# Micro_controller_Board_AS-2.net
KiCad netlist of a schematic drawn in EAGLE
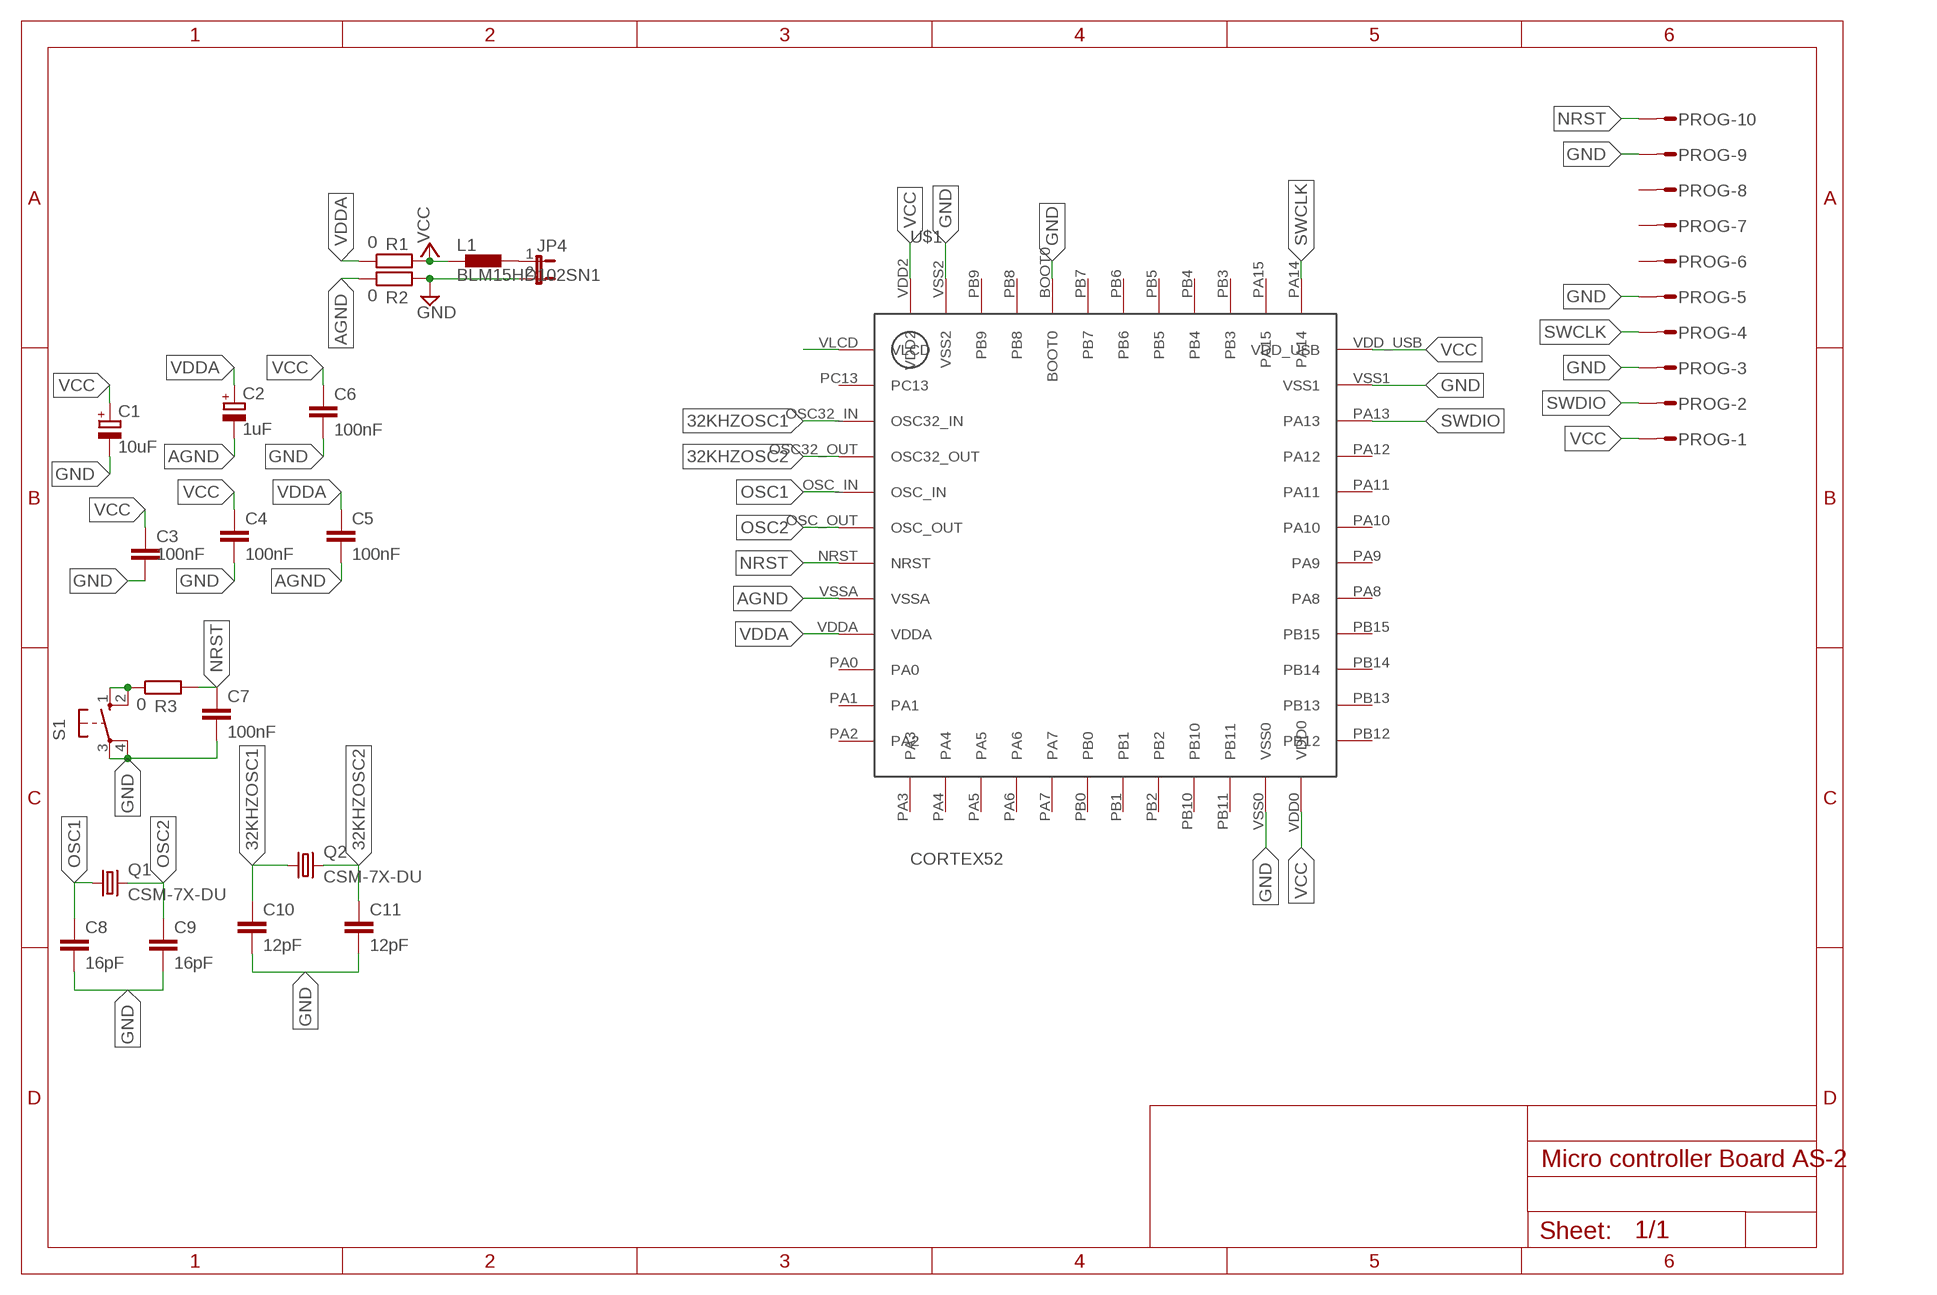
[diagram p0: schematic, sheet 1]

(export (version "E")
  (design (tool "Eeschema 10.0.6"))
  (components
    (comp (ref "C1")
      (value "10uF")
      (footprint "eagle-import:139CLL-2R")
      (libsource (lib "eagle-import") (part "CPOL-EU139CLL-2R"))
    )
    (comp (ref "C2")
      (value "1uF")
      (footprint "eagle-import:139CLL-2R")
      (libsource (lib "eagle-import") (part "CPOL-EU139CLL-2R"))
    )
    (comp (ref "C3")
      (value "100nF")
      (footprint "eagle-import:C0805")
      (libsource (lib "eagle-import") (part "C-EUC0805"))
    )
    (comp (ref "C4")
      (value "100nF")
      (footprint "eagle-import:C0805")
      (libsource (lib "eagle-import") (part "C-EUC0805"))
    )
    (comp (ref "C5")
      (value "100nF")
      (footprint "eagle-import:C0805")
      (libsource (lib "eagle-import") (part "C-EUC0805"))
    )
    (comp (ref "C6")
      (value "100nF")
      (footprint "eagle-import:C0805")
      (libsource (lib "eagle-import") (part "C-EUC0805"))
    )
    (comp (ref "C7")
      (value "100nF")
      (footprint "eagle-import:C0805")
      (libsource (lib "eagle-import") (part "C-EUC0805"))
    )
    (comp (ref "C8")
      (value "16pF")
      (footprint "eagle-import:C0805")
      (libsource (lib "eagle-import") (part "C-EUC0805"))
    )
    (comp (ref "C9")
      (value "16pF")
      (footprint "eagle-import:C0805")
      (libsource (lib "eagle-import") (part "C-EUC0805"))
    )
    (comp (ref "C10")
      (value "12pF")
      (footprint "eagle-import:C0805")
      (libsource (lib "eagle-import") (part "C-EUC0805"))
    )
    (comp (ref "C11")
      (value "12pF")
      (footprint "eagle-import:C0805")
      (libsource (lib "eagle-import") (part "C-EUC0805"))
    )
    (comp (ref "JP4")
      (value "JP1E")
      (footprint "eagle-import:JP1")
      (libsource (lib "eagle-import") (part "JP1E"))
    )
    (comp (ref "L1")
      (value "BLM15HD102SN1")
      (footprint "eagle-import:0402")
      (libsource (lib "eagle-import") (part "BLM15HD102SN1"))
    )
    (comp (ref "PROG")
      (value "S10P")
      (footprint "eagle-import:S10P")
      (libsource (lib "eagle-import") (part "S10P"))
    )
    (comp (ref "Q1")
      (value "CSM-7X-DU")
      (footprint "eagle-import:CSM-7X-DU")
      (libsource (lib "eagle-import") (part "CSM-7X-DU"))
    )
    (comp (ref "Q2")
      (value "CSM-7X-DU")
      (footprint "eagle-import:CSM-7X-DU")
      (libsource (lib "eagle-import") (part "CSM-7X-DU"))
    )
    (comp (ref "R1")
      (value "0")
      (footprint "eagle-import:R0805")
      (libsource (lib "eagle-import") (part "R-EU_R0805"))
    )
    (comp (ref "R2")
      (value "0")
      (footprint "eagle-import:R0805")
      (libsource (lib "eagle-import") (part "R-EU_R0805"))
    )
    (comp (ref "R3")
      (value "0")
      (footprint "eagle-import:R0805")
      (libsource (lib "eagle-import") (part "R-EU_R0805"))
    )
    (comp (ref "S1")
      (value "10-XX")
      (footprint "eagle-import:B3F-10XX")
      (fields (field (name "MPN") "B3F-1000"))
      (libsource (lib "eagle-import") (part "10-XX"))
    )
    (comp (ref "U$1")
      (value "CORTEX52")
      (footprint "eagle-import:CORTEX52")
      (libsource (lib "eagle-import") (part "CORTEX52"))
    )
  )
  (nets
    (net (code "1") (name "32KHZOSC1") (class "Default")
      (node (ref "C10") (pin "1") (pinfunction "1_1") (pintype "passive"))
      (node (ref "Q2") (pin "1") (pinfunction "1_1") (pintype "passive"))
      (node (ref "U$1") (pin "OSC32_IN") (pinfunction "OSC32_IN_OSC32_IN") (pintype "bidirectional"))
    )
    (net (code "2") (name "32KHZOSC2") (class "Default")
      (node (ref "C11") (pin "1") (pinfunction "1_1") (pintype "passive"))
      (node (ref "Q2") (pin "2") (pinfunction "2_2") (pintype "passive"))
      (node (ref "U$1") (pin "OSC32_OUT") (pinfunction "OSC32_OUT_OSC32_OUT") (pintype "bidirectional"))
    )
    (net (code "3") (name "AGND") (class "Default")
      (node (ref "C2") (pin "-") (pinfunction "-_-") (pintype "passive"))
      (node (ref "C5") (pin "2") (pinfunction "2_2") (pintype "passive"))
      (node (ref "R2") (pin "1") (pinfunction "1_1") (pintype "passive"))
      (node (ref "U$1") (pin "VSSA") (pinfunction "VSSA_VSSA") (pintype "bidirectional"))
    )
    (net (code "4") (name "GND") (class "Default")
      (node (ref "C1") (pin "-") (pinfunction "-_-") (pintype "passive"))
      (node (ref "C10") (pin "2") (pinfunction "2_2") (pintype "passive"))
      (node (ref "C11") (pin "2") (pinfunction "2_2") (pintype "passive"))
      (node (ref "C3") (pin "2") (pinfunction "2_2") (pintype "passive"))
      (node (ref "C4") (pin "2") (pinfunction "2_2") (pintype "passive"))
      (node (ref "C6") (pin "2") (pinfunction "2_2") (pintype "passive"))
      (node (ref "C7") (pin "2") (pinfunction "2_2") (pintype "passive"))
      (node (ref "C8") (pin "2") (pinfunction "2_2") (pintype "passive"))
      (node (ref "C9") (pin "2") (pinfunction "2_2") (pintype "passive"))
      (node (ref "JP4") (pin "2") (pinfunction "2_2") (pintype "passive"))
      (node (ref "PROG") (pin "3") (pinfunction "S_3") (pintype "passive"))
      (node (ref "PROG") (pin "5") (pinfunction "S_5") (pintype "passive"))
      (node (ref "PROG") (pin "9") (pinfunction "S_9") (pintype "passive"))
      (node (ref "R2") (pin "2") (pinfunction "2_2") (pintype "passive"))
      (node (ref "S1") (pin "3") (pinfunction "P_3") (pintype "passive"))
      (node (ref "S1") (pin "4") (pinfunction "P1_4") (pintype "passive"))
      (node (ref "U$1") (pin "BOOT0") (pinfunction "BOOT0_BOOT0") (pintype "bidirectional"))
      (node (ref "U$1") (pin "VSS0") (pinfunction "VSS0_VSS0") (pintype "bidirectional"))
      (node (ref "U$1") (pin "VSS1") (pinfunction "VSS1_VSS1") (pintype "bidirectional"))
      (node (ref "U$1") (pin "VSS2") (pinfunction "VSS2_VSS2") (pintype "bidirectional"))
    )
    (net (code "5") (name "NRST") (class "Default")
      (node (ref "C7") (pin "1") (pinfunction "1_1") (pintype "passive"))
      (node (ref "PROG") (pin "10") (pinfunction "S_10") (pintype "passive"))
      (node (ref "R3") (pin "2") (pinfunction "2_2") (pintype "passive"))
      (node (ref "U$1") (pin "NRST") (pinfunction "NRST_NRST") (pintype "bidirectional"))
    )
    (net (code "6") (name "Net-(JP4-Pad1)") (class "Default")
      (node (ref "JP4") (pin "1") (pinfunction "1_1") (pintype "passive"))
      (node (ref "L1") (pin "2") (pinfunction "2_2") (pintype "passive"))
    )
    (net (code "7") (name "Net-(S1-S)") (class "Default")
      (node (ref "R3") (pin "1") (pinfunction "1_1") (pintype "passive"))
      (node (ref "S1") (pin "1") (pinfunction "S_1") (pintype "passive"))
      (node (ref "S1") (pin "2") (pinfunction "S1_2") (pintype "passive"))
    )
    (net (code "8") (name "OSC1") (class "Default")
      (node (ref "C8") (pin "1") (pinfunction "1_1") (pintype "passive"))
      (node (ref "Q1") (pin "1") (pinfunction "1_1") (pintype "passive"))
      (node (ref "U$1") (pin "OSC_IN") (pinfunction "OSC_IN_OSC_IN") (pintype "bidirectional"))
    )
    (net (code "9") (name "OSC2") (class "Default")
      (node (ref "C9") (pin "1") (pinfunction "1_1") (pintype "passive"))
      (node (ref "Q1") (pin "2") (pinfunction "2_2") (pintype "passive"))
      (node (ref "U$1") (pin "OSC_OUT") (pinfunction "OSC_OUT_OSC_OUT") (pintype "bidirectional"))
    )
    (net (code "10") (name "SWCLK") (class "Default")
      (node (ref "PROG") (pin "4") (pinfunction "S_4") (pintype "passive"))
      (node (ref "U$1") (pin "PA14") (pinfunction "PA14_PA14") (pintype "bidirectional"))
    )
    (net (code "11") (name "SWDIO") (class "Default")
      (node (ref "PROG") (pin "2") (pinfunction "S_2") (pintype "passive"))
      (node (ref "U$1") (pin "PA13") (pinfunction "PA13_PA13") (pintype "bidirectional"))
    )
    (net (code "12") (name "VCC") (class "Default")
      (node (ref "C1") (pin "+") (pinfunction "+_+") (pintype "passive"))
      (node (ref "C3") (pin "1") (pinfunction "1_1") (pintype "passive"))
      (node (ref "C4") (pin "1") (pinfunction "1_1") (pintype "passive"))
      (node (ref "C6") (pin "1") (pinfunction "1_1") (pintype "passive"))
      (node (ref "L1") (pin "1") (pinfunction "1_1") (pintype "passive"))
      (node (ref "PROG") (pin "1") (pinfunction "S_1") (pintype "passive"))
      (node (ref "R1") (pin "2") (pinfunction "2_2") (pintype "passive"))
      (node (ref "U$1") (pin "VDD0") (pinfunction "VDD0_VDD0") (pintype "bidirectional"))
      (node (ref "U$1") (pin "VDD2") (pinfunction "VDD2_VDD2") (pintype "bidirectional"))
      (node (ref "U$1") (pin "VDD_USB") (pinfunction "VDD_USB_VDD_USB") (pintype "bidirectional"))
    )
    (net (code "13") (name "VDDA") (class "Default")
      (node (ref "C2") (pin "+") (pinfunction "+_+") (pintype "passive"))
      (node (ref "C5") (pin "1") (pinfunction "1_1") (pintype "passive"))
      (node (ref "R1") (pin "1") (pinfunction "1_1") (pintype "passive"))
      (node (ref "U$1") (pin "VDDA") (pinfunction "VDDA_VDDA") (pintype "bidirectional"))
    )
    (net (code "14") (name "unconnected-(PROGG-S-Pad6)") (class "Default")
      (node (ref "PROG") (pin "6") (pinfunction "S_6") (pintype "passive"))
    )
    (net (code "15") (name "unconnected-(PROGH-S-Pad7)") (class "Default")
      (node (ref "PROG") (pin "7") (pinfunction "S_7") (pintype "passive"))
    )
    (net (code "16") (name "unconnected-(PROGI-S-Pad8)") (class "Default")
      (node (ref "PROG") (pin "8") (pinfunction "S_8") (pintype "passive"))
    )
    (net (code "17") (name "unconnected-(U$1-PadPA0)") (class "Default")
      (node (ref "U$1") (pin "PA0") (pinfunction "PA0_PA0") (pintype "bidirectional"))
    )
    (net (code "18") (name "unconnected-(U$1-PadPA1)") (class "Default")
      (node (ref "U$1") (pin "PA1") (pinfunction "PA1_PA1") (pintype "bidirectional"))
    )
    (net (code "19") (name "unconnected-(U$1-PadPA2)") (class "Default")
      (node (ref "U$1") (pin "PA2") (pinfunction "PA2_PA2") (pintype "bidirectional"))
    )
    (net (code "20") (name "unconnected-(U$1-PadPA3)") (class "Default")
      (node (ref "U$1") (pin "PA3") (pinfunction "PA3_PA3") (pintype "bidirectional"))
    )
    (net (code "21") (name "unconnected-(U$1-PadPA4)") (class "Default")
      (node (ref "U$1") (pin "PA4") (pinfunction "PA4_PA4") (pintype "bidirectional"))
    )
    (net (code "22") (name "unconnected-(U$1-PadPA5)") (class "Default")
      (node (ref "U$1") (pin "PA5") (pinfunction "PA5_PA5") (pintype "bidirectional"))
    )
    (net (code "23") (name "unconnected-(U$1-PadPA6)") (class "Default")
      (node (ref "U$1") (pin "PA6") (pinfunction "PA6_PA6") (pintype "bidirectional"))
    )
    (net (code "24") (name "unconnected-(U$1-PadPA7)") (class "Default")
      (node (ref "U$1") (pin "PA7") (pinfunction "PA7_PA7") (pintype "bidirectional"))
    )
    (net (code "25") (name "unconnected-(U$1-PadPA8)") (class "Default")
      (node (ref "U$1") (pin "PA8") (pinfunction "PA8_PA8") (pintype "bidirectional"))
    )
    (net (code "26") (name "unconnected-(U$1-PadPA9)") (class "Default")
      (node (ref "U$1") (pin "PA9") (pinfunction "PA9_PA9") (pintype "bidirectional"))
    )
    (net (code "27") (name "unconnected-(U$1-PadPA10)") (class "Default")
      (node (ref "U$1") (pin "PA10") (pinfunction "PA10_PA10") (pintype "bidirectional"))
    )
    (net (code "28") (name "unconnected-(U$1-PadPA11)") (class "Default")
      (node (ref "U$1") (pin "PA11") (pinfunction "PA11_PA11") (pintype "bidirectional"))
    )
    (net (code "29") (name "unconnected-(U$1-PadPA12)") (class "Default")
      (node (ref "U$1") (pin "PA12") (pinfunction "PA12_PA12") (pintype "bidirectional"))
    )
    (net (code "30") (name "unconnected-(U$1-PadPA15)") (class "Default")
      (node (ref "U$1") (pin "PA15") (pinfunction "PA15_PA15") (pintype "bidirectional"))
    )
    (net (code "31") (name "unconnected-(U$1-PadPB0)") (class "Default")
      (node (ref "U$1") (pin "PB0") (pinfunction "PB0_PB0") (pintype "bidirectional"))
    )
    (net (code "32") (name "unconnected-(U$1-PadPB1)") (class "Default")
      (node (ref "U$1") (pin "PB1") (pinfunction "PB1_PB1") (pintype "bidirectional"))
    )
    (net (code "33") (name "unconnected-(U$1-PadPB2)") (class "Default")
      (node (ref "U$1") (pin "PB2") (pinfunction "PB2_PB2") (pintype "bidirectional"))
    )
    (net (code "34") (name "unconnected-(U$1-PadPB3)") (class "Default")
      (node (ref "U$1") (pin "PB3") (pinfunction "PB3_PB3") (pintype "bidirectional"))
    )
    (net (code "35") (name "unconnected-(U$1-PadPB4)") (class "Default")
      (node (ref "U$1") (pin "PB4") (pinfunction "PB4_PB4") (pintype "bidirectional"))
    )
    (net (code "36") (name "unconnected-(U$1-PadPB5)") (class "Default")
      (node (ref "U$1") (pin "PB5") (pinfunction "PB5_PB5") (pintype "bidirectional"))
    )
    (net (code "37") (name "unconnected-(U$1-PadPB6)") (class "Default")
      (node (ref "U$1") (pin "PB6") (pinfunction "PB6_PB6") (pintype "bidirectional"))
    )
    (net (code "38") (name "unconnected-(U$1-PadPB7)") (class "Default")
      (node (ref "U$1") (pin "PB7") (pinfunction "PB7_PB7") (pintype "bidirectional"))
    )
    (net (code "39") (name "unconnected-(U$1-PadPB8)") (class "Default")
      (node (ref "U$1") (pin "PB8") (pinfunction "PB8_PB8") (pintype "bidirectional"))
    )
    (net (code "40") (name "unconnected-(U$1-PadPB9)") (class "Default")
      (node (ref "U$1") (pin "PB9") (pinfunction "PB9_PB9") (pintype "bidirectional"))
    )
    (net (code "41") (name "unconnected-(U$1-PadPB10)") (class "Default")
      (node (ref "U$1") (pin "PB10") (pinfunction "PB10_PB10") (pintype "bidirectional"))
    )
    (net (code "42") (name "unconnected-(U$1-PadPB11)") (class "Default")
      (node (ref "U$1") (pin "PB11") (pinfunction "PB11_PB11") (pintype "bidirectional"))
    )
    (net (code "43") (name "unconnected-(U$1-PadPB12)") (class "Default")
      (node (ref "U$1") (pin "PB12") (pinfunction "PB12_PB12") (pintype "bidirectional"))
    )
    (net (code "44") (name "unconnected-(U$1-PadPB13)") (class "Default")
      (node (ref "U$1") (pin "PB13") (pinfunction "PB13_PB13") (pintype "bidirectional"))
    )
    (net (code "45") (name "unconnected-(U$1-PadPB14)") (class "Default")
      (node (ref "U$1") (pin "PB14") (pinfunction "PB14_PB14") (pintype "bidirectional"))
    )
    (net (code "46") (name "unconnected-(U$1-PadPB15)") (class "Default")
      (node (ref "U$1") (pin "PB15") (pinfunction "PB15_PB15") (pintype "bidirectional"))
    )
    (net (code "47") (name "unconnected-(U$1-PadPC13)") (class "Default")
      (node (ref "U$1") (pin "PC13") (pinfunction "PC13_PC13") (pintype "bidirectional"))
    )
    (net (code "48") (name "unconnected-(U$1-PadVLCD)") (class "Default")
      (node (ref "U$1") (pin "VLCD") (pinfunction "VLCD_VLCD") (pintype "bidirectional"))
    )
  )
)
